# EnvironmentMonitorV5.net
KiCad netlist of a schematic drawn in EAGLE
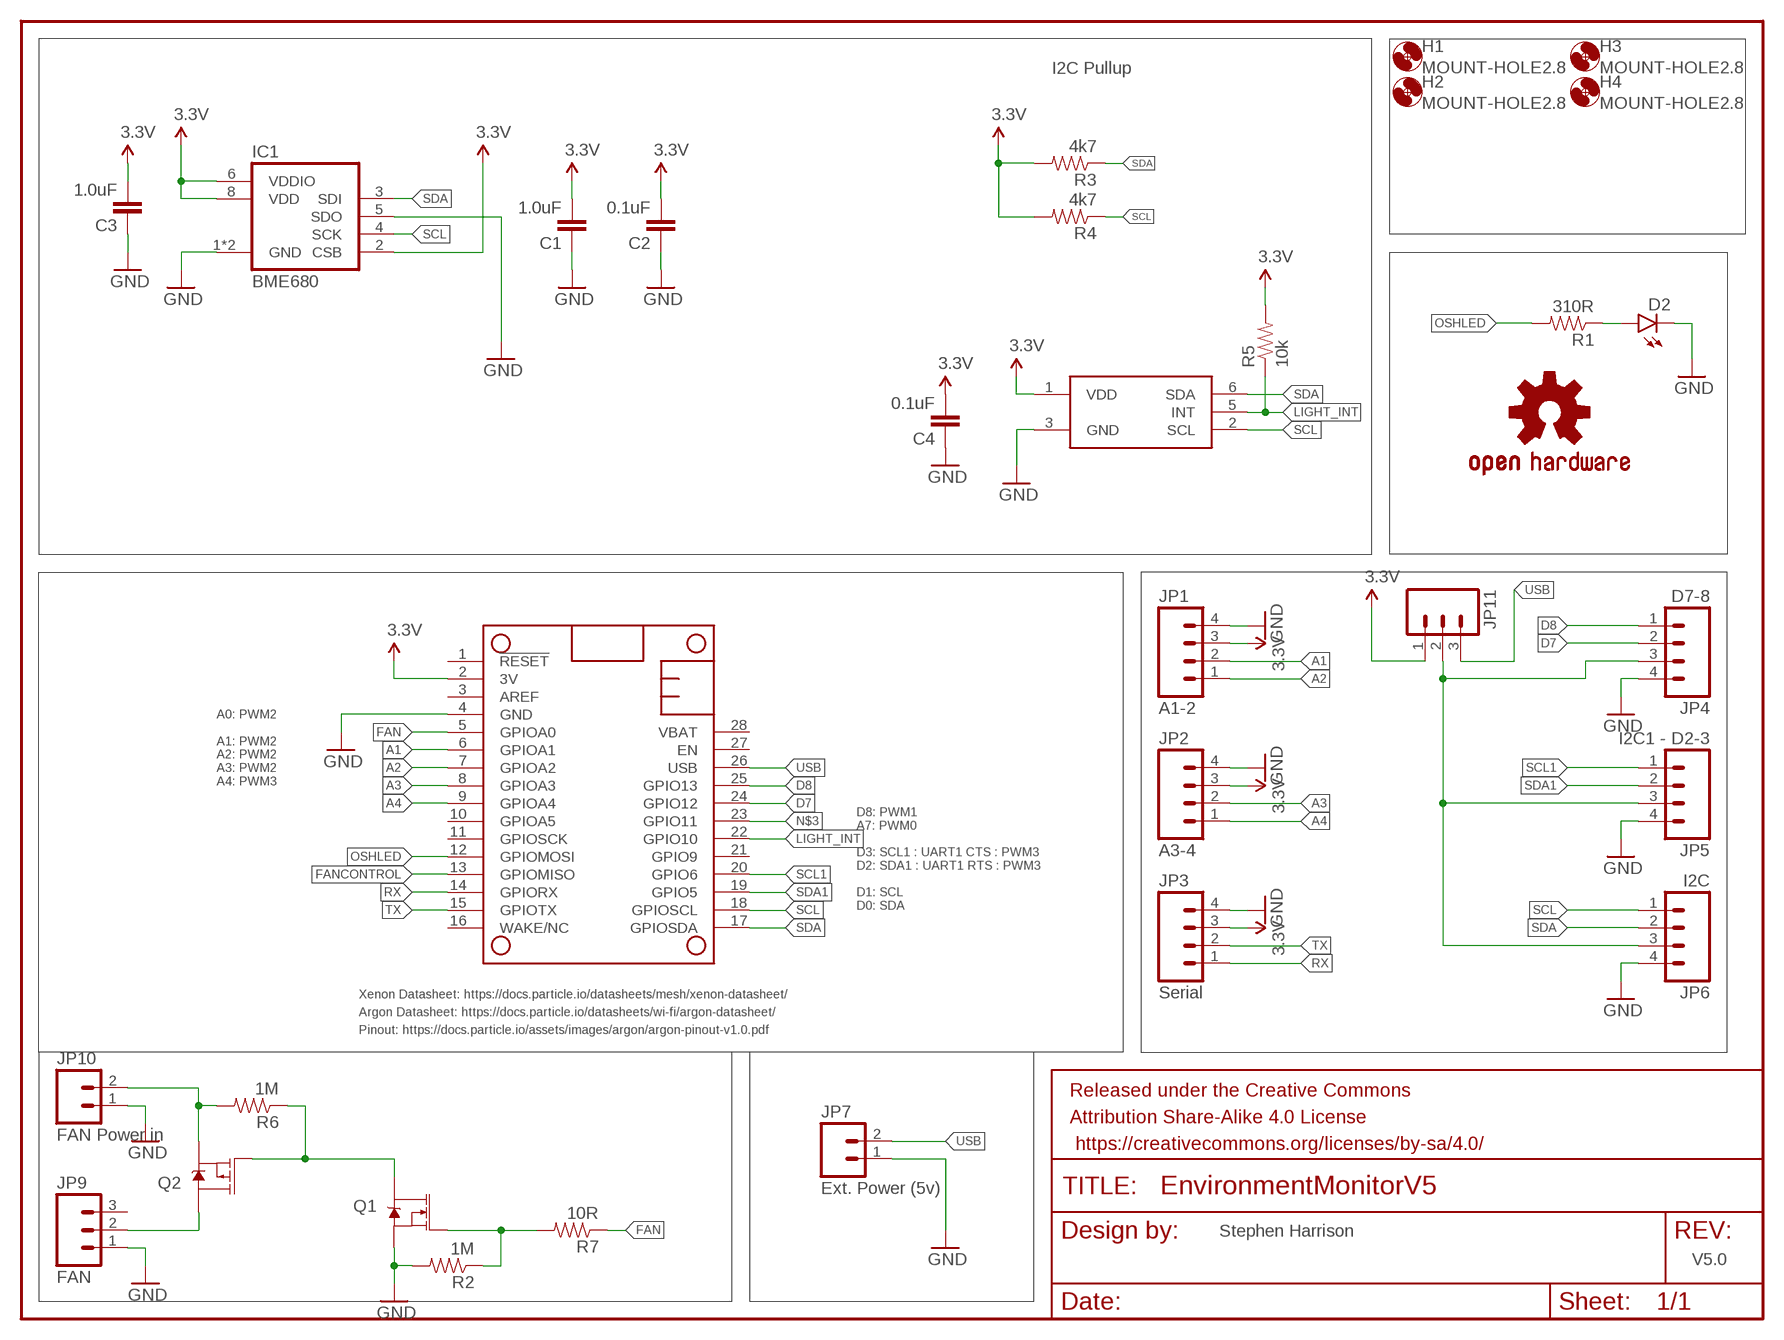
[diagram p0: schematic, sheet 1]

(export (version "E")
  (design (tool "Eeschema 10.0.6"))
  (components
    (comp (ref "C1")
      (value "1.0uF")
      (footprint "eagle-import:0805-CAP")
      (libsource (lib "eagle-import") (part "1.0UF-25V-+80/-20(0805){dblquote}"))
    )
    (comp (ref "C2")
      (value "0.1uF")
      (footprint "eagle-import:0805-CAP")
      (libsource (lib "eagle-import") (part "1.0UF-25V-+80/-20(0805){dblquote}"))
    )
    (comp (ref "C3")
      (value "1.0uF")
      (footprint "eagle-import:0805-CAP")
      (libsource (lib "eagle-import") (part "1.0UF-25V-+80/-20(0805){dblquote}"))
    )
    (comp (ref "C4")
      (value "0.1uF")
      (footprint "eagle-import:0805-CAP")
      (libsource (lib "eagle-import") (part "1.0UF-25V-+80/-20(0805){dblquote}"))
    )
    (comp (ref "D2")
      (value "LED1206-BOTTOM")
      (footprint "eagle-import:LED-1206-BOTTOM")
      (libsource (lib "eagle-import") (part "LED1206-BOTTOM"))
    )
    (comp (ref "FRAME1")
      (value "FRAME-LETTER")
      (footprint "eagle-import:CREATIVE_COMMONS")
      (libsource (lib "eagle-import") (part "FRAME-LETTER"))
    )
    (comp (ref "H1")
      (value "MOUNT-HOLE2.8")
      (footprint "eagle-import:2,8")
      (libsource (lib "eagle-import") (part "MOUNT-HOLE2.8"))
    )
    (comp (ref "H2")
      (value "MOUNT-HOLE2.8")
      (footprint "eagle-import:2,8")
      (libsource (lib "eagle-import") (part "MOUNT-HOLE2.8"))
    )
    (comp (ref "H3")
      (value "MOUNT-HOLE2.8")
      (footprint "eagle-import:2,8")
      (libsource (lib "eagle-import") (part "MOUNT-HOLE2.8"))
    )
    (comp (ref "H4")
      (value "MOUNT-HOLE2.8")
      (footprint "eagle-import:2,8")
      (libsource (lib "eagle-import") (part "MOUNT-HOLE2.8"))
    )
    (comp (ref "IC1")
      (value "BME680")
      (footprint "eagle-import:BME680")
      (libsource (lib "eagle-import") (part "BME680"))
    )
    (comp (ref "IC2")
      (value "TCS3472")
      (footprint "eagle-import:FN-6")
      (libsource (lib "eagle-import") (part "TCS3472"))
    )
    (comp (ref "JP1")
      (value "A1-2")
      (footprint "eagle-import:JST-4-PTH-VERT")
      (libsource (lib "eagle-import") (part "M04JST-PTH-VERT"))
    )
    (comp (ref "JP2")
      (value "A3-4")
      (footprint "eagle-import:JST-4-PTH-VERT")
      (libsource (lib "eagle-import") (part "M04JST-PTH-VERT"))
    )
    (comp (ref "JP3")
      (value "Serial")
      (footprint "eagle-import:JST-4-PTH-VERT")
      (libsource (lib "eagle-import") (part "M04JST-PTH-VERT"))
    )
    (comp (ref "JP4")
      (value "D7-8")
      (footprint "eagle-import:JST-4-PTH-VERT")
      (libsource (lib "eagle-import") (part "M04JST-PTH-VERT"))
    )
    (comp (ref "JP5")
      (value "I2C1 - D2-3")
      (footprint "eagle-import:JST-4-PTH-VERT")
      (libsource (lib "eagle-import") (part "M04JST-PTH-VERT"))
    )
    (comp (ref "JP6")
      (value "I2C")
      (footprint "eagle-import:JST-4-PTH-VERT")
      (libsource (lib "eagle-import") (part "M04JST-PTH-VERT"))
    )
    (comp (ref "JP7")
      (value "Ext. Power (5v)")
      (footprint "eagle-import:MOLEX-1X2_LOCK")
      (libsource (lib "eagle-import") (part "M02POLAR_LOCK"))
    )
    (comp (ref "JP9")
      (value "FAN")
      (footprint "eagle-import:MOLEX-1X3")
      (libsource (lib "eagle-import") (part "M03POLAR"))
    )
    (comp (ref "JP10")
      (value "FAN Power in")
      (footprint "eagle-import:MOLEX-1X2_LOCK")
      (libsource (lib "eagle-import") (part "M02POLAR_LOCK"))
    )
    (comp (ref "JP11")
      (value "M03PTH")
      (footprint "eagle-import:1X03")
      (libsource (lib "eagle-import") (part "M03PTH"))
    )
    (comp (ref "LOGO1")
      (value "OSHW-LOGOM")
      (footprint "eagle-import:OSHW-LOGO-M")
      (libsource (lib "eagle-import") (part "OSHW-LOGOM"))
    )
    (comp (ref "MS1")
      (value "FEATHERWING_NODIM")
      (footprint "eagle-import:FEATHERWING_DIM")
      (libsource (lib "eagle-import") (part "FEATHERWING_NODIM"))
    )
    (comp (ref "Q1")
      (value "220mA/50V/3.5Ω")
      (footprint "eagle-import:SOT23-3")
      (libsource (lib "eagle-import") (part "MOSFET-NCH-BSS138"))
    )
    (comp (ref "Q2")
      (value "4.3A/20V/54mΩ")
      (footprint "eagle-import:SOT23-3")
      (libsource (lib "eagle-import") (part "MOSFET_PCH-IRLML2244"))
    )
    (comp (ref "R1")
      (value "310R")
      (footprint "eagle-import:0805")
      (libsource (lib "eagle-import") (part "RESISTOR0805-RES"))
    )
    (comp (ref "R2")
      (value "1M")
      (footprint "eagle-import:0805")
      (libsource (lib "eagle-import") (part "RESISTOR0805-RES"))
    )
    (comp (ref "R3")
      (value "4k7")
      (footprint "eagle-import:0805")
      (libsource (lib "eagle-import") (part "RESISTOR0805-RES"))
    )
    (comp (ref "R4")
      (value "4k7")
      (footprint "eagle-import:0805")
      (libsource (lib "eagle-import") (part "RESISTOR0805-RES"))
    )
    (comp (ref "R5")
      (value "10k")
      (footprint "eagle-import:0805")
      (libsource (lib "eagle-import") (part "RESISTOR0805-RES"))
    )
    (comp (ref "R6")
      (value "1M")
      (footprint "eagle-import:0805")
      (libsource (lib "eagle-import") (part "RESISTOR0805-RES"))
    )
    (comp (ref "R7")
      (value "10R")
      (footprint "eagle-import:0805")
      (libsource (lib "eagle-import") (part "RESISTOR0805-RES"))
    )
  )
  (nets
    (net (code "1") (name "/VBAT") (class "Default")
      (node (ref "MS1") (pin "28") (pinfunction "VBAT_28") (pintype "power_in"))
    )
    (net (code "2") (name "3.3V") (class "Default")
      (node (ref "C1") (pin "2") (pinfunction "2_2") (pintype "passive"))
      (node (ref "C2") (pin "2") (pinfunction "2_2") (pintype "passive"))
      (node (ref "C3") (pin "2") (pinfunction "2_2") (pintype "passive"))
      (node (ref "C4") (pin "2") (pinfunction "2_2") (pintype "passive"))
      (node (ref "IC1") (pin "2") (pinfunction "CSB_2") (pintype "input"))
      (node (ref "IC1") (pin "6") (pinfunction "VDDIO_6") (pintype "power_in"))
      (node (ref "IC1") (pin "8") (pinfunction "VDD_8") (pintype "power_in"))
      (node (ref "IC2") (pin "1") (pinfunction "VDD_1") (pintype "bidirectional"))
      (node (ref "JP1") (pin "3") (pinfunction "3_3") (pintype "passive"))
      (node (ref "JP11") (pin "1") (pinfunction "1_1") (pintype "passive"))
      (node (ref "JP2") (pin "3") (pinfunction "3_3") (pintype "passive"))
      (node (ref "JP3") (pin "3") (pinfunction "3_3") (pintype "passive"))
      (node (ref "MS1") (pin "2") (pinfunction "3V_2") (pintype "power_in"))
      (node (ref "R3") (pin "2") (pinfunction "2_2") (pintype "passive"))
      (node (ref "R4") (pin "2") (pinfunction "2_2") (pintype "passive"))
      (node (ref "R5") (pin "2") (pinfunction "2_2") (pintype "passive"))
    )
    (net (code "3") (name "A1") (class "Default")
      (node (ref "JP1") (pin "2") (pinfunction "2_2") (pintype "passive"))
      (node (ref "MS1") (pin "6") (pinfunction "GPIOA1_6") (pintype "bidirectional"))
    )
    (net (code "4") (name "A2") (class "Default")
      (node (ref "JP1") (pin "1") (pinfunction "1_1") (pintype "passive"))
      (node (ref "MS1") (pin "7") (pinfunction "GPIOA2_7") (pintype "bidirectional"))
    )
    (net (code "5") (name "A3") (class "Default")
      (node (ref "JP2") (pin "2") (pinfunction "2_2") (pintype "passive"))
      (node (ref "MS1") (pin "8") (pinfunction "GPIOA3_8") (pintype "bidirectional"))
    )
    (net (code "6") (name "A4") (class "Default")
      (node (ref "JP2") (pin "1") (pinfunction "1_1") (pintype "passive"))
      (node (ref "MS1") (pin "9") (pinfunction "GPIOA4_9") (pintype "bidirectional"))
    )
    (net (code "7") (name "D7") (class "Default")
      (node (ref "JP4") (pin "2") (pinfunction "2_2") (pintype "passive"))
      (node (ref "MS1") (pin "24") (pinfunction "GPIO12_24") (pintype "bidirectional"))
    )
    (net (code "8") (name "D8") (class "Default")
      (node (ref "JP4") (pin "1") (pinfunction "1_1") (pintype "passive"))
      (node (ref "MS1") (pin "25") (pinfunction "GPIO13_25") (pintype "bidirectional"))
    )
    (net (code "9") (name "FAN") (class "Default")
      (node (ref "MS1") (pin "5") (pinfunction "GPIOA0_5") (pintype "bidirectional"))
      (node (ref "R7") (pin "1") (pinfunction "1_1") (pintype "passive"))
    )
    (net (code "10") (name "FANCONTROL") (class "Default")
      (node (ref "MS1") (pin "13") (pinfunction "GPIOMISO_13") (pintype "bidirectional"))
    )
    (net (code "11") (name "GND") (class "Default")
      (node (ref "C1") (pin "1") (pinfunction "1_1") (pintype "passive"))
      (node (ref "C2") (pin "1") (pinfunction "1_1") (pintype "passive"))
      (node (ref "C3") (pin "1") (pinfunction "1_1") (pintype "passive"))
      (node (ref "C4") (pin "1") (pinfunction "1_1") (pintype "passive"))
      (node (ref "D2") (pin "C") (pinfunction "C_C") (pintype "passive"))
      (node (ref "IC1") (pin "1") (pinfunction "GND_1") (pintype "power_in"))
      (node (ref "IC1") (pin "5") (pinfunction "SDO_5") (pintype "output"))
      (node (ref "IC1") (pin "7") (pinfunction "GND_7") (pintype "power_in"))
      (node (ref "IC2") (pin "3") (pinfunction "GND_3") (pintype "bidirectional"))
      (node (ref "JP1") (pin "4") (pinfunction "4_4") (pintype "passive"))
      (node (ref "JP10") (pin "1") (pinfunction "1_1") (pintype "passive"))
      (node (ref "JP2") (pin "4") (pinfunction "4_4") (pintype "passive"))
      (node (ref "JP3") (pin "4") (pinfunction "4_4") (pintype "passive"))
      (node (ref "JP4") (pin "4") (pinfunction "4_4") (pintype "passive"))
      (node (ref "JP5") (pin "4") (pinfunction "4_4") (pintype "passive"))
      (node (ref "JP6") (pin "4") (pinfunction "4_4") (pintype "passive"))
      (node (ref "JP7") (pin "1") (pinfunction "1_1") (pintype "passive"))
      (node (ref "JP9") (pin "1") (pinfunction "1_1") (pintype "passive"))
      (node (ref "MS1") (pin "4") (pinfunction "GND_4") (pintype "power_in"))
      (node (ref "Q1") (pin "2") (pinfunction "S_2") (pintype "bidirectional"))
      (node (ref "R2") (pin "2") (pinfunction "2_2") (pintype "passive"))
    )
    (net (code "12") (name "LIGHT_INT") (class "Default")
      (node (ref "IC2") (pin "5") (pinfunction "INT_5") (pintype "bidirectional"))
      (node (ref "MS1") (pin "22") (pinfunction "GPIO10_22") (pintype "bidirectional"))
      (node (ref "R5") (pin "1") (pinfunction "1_1") (pintype "passive"))
    )
    (net (code "13") (name "N$3") (class "Default")
      (node (ref "MS1") (pin "23") (pinfunction "GPIO11_23") (pintype "bidirectional"))
    )
    (net (code "14") (name "Net-(D2-PadA)") (class "Default")
      (node (ref "D2") (pin "A") (pinfunction "A_A") (pintype "passive"))
      (node (ref "R1") (pin "1") (pinfunction "1_1") (pintype "passive"))
    )
    (net (code "15") (name "Net-(JP11-Pad2)") (class "Default")
      (node (ref "JP11") (pin "2") (pinfunction "2_2") (pintype "passive"))
      (node (ref "JP4") (pin "3") (pinfunction "3_3") (pintype "passive"))
      (node (ref "JP5") (pin "3") (pinfunction "3_3") (pintype "passive"))
      (node (ref "JP6") (pin "3") (pinfunction "3_3") (pintype "passive"))
    )
    (net (code "16") (name "Net-(Q1-D)") (class "Default")
      (node (ref "Q1") (pin "3") (pinfunction "D_3") (pintype "bidirectional"))
      (node (ref "Q2") (pin "1") (pinfunction "G_1") (pintype "bidirectional"))
      (node (ref "R6") (pin "1") (pinfunction "1_1") (pintype "passive"))
    )
    (net (code "17") (name "Net-(Q1-G)") (class "Default")
      (node (ref "Q1") (pin "1") (pinfunction "G_1") (pintype "bidirectional"))
      (node (ref "R2") (pin "1") (pinfunction "1_1") (pintype "passive"))
      (node (ref "R7") (pin "2") (pinfunction "2_2") (pintype "passive"))
    )
    (net (code "18") (name "Net-(Q2-D)") (class "Default")
      (node (ref "JP9") (pin "2") (pinfunction "2_2") (pintype "passive"))
      (node (ref "Q2") (pin "3") (pinfunction "D_3") (pintype "bidirectional"))
    )
    (net (code "19") (name "Net-(Q2-S)") (class "Default")
      (node (ref "JP10") (pin "2") (pinfunction "2_2") (pintype "passive"))
      (node (ref "Q2") (pin "2") (pinfunction "S_2") (pintype "bidirectional"))
      (node (ref "R6") (pin "2") (pinfunction "2_2") (pintype "passive"))
    )
    (net (code "20") (name "OSHLED") (class "Default")
      (node (ref "MS1") (pin "12") (pinfunction "GPIOMOSI_12") (pintype "bidirectional"))
      (node (ref "R1") (pin "2") (pinfunction "2_2") (pintype "passive"))
    )
    (net (code "21") (name "RX") (class "Default")
      (node (ref "JP3") (pin "1") (pinfunction "1_1") (pintype "passive"))
      (node (ref "MS1") (pin "14") (pinfunction "GPIORX_14") (pintype "bidirectional"))
    )
    (net (code "22") (name "SCL") (class "Default")
      (node (ref "IC1") (pin "4") (pinfunction "SCK_4") (pintype "input"))
      (node (ref "IC2") (pin "2") (pinfunction "SCL_2") (pintype "bidirectional"))
      (node (ref "JP6") (pin "1") (pinfunction "1_1") (pintype "passive"))
      (node (ref "MS1") (pin "18") (pinfunction "GPIOSCL_18") (pintype "bidirectional"))
      (node (ref "R4") (pin "1") (pinfunction "1_1") (pintype "passive"))
    )
    (net (code "23") (name "SCL1") (class "Default")
      (node (ref "JP5") (pin "1") (pinfunction "1_1") (pintype "passive"))
      (node (ref "MS1") (pin "20") (pinfunction "GPIO6_20") (pintype "bidirectional"))
    )
    (net (code "24") (name "SDA") (class "Default")
      (node (ref "IC1") (pin "3") (pinfunction "SDI_3") (pintype "input"))
      (node (ref "IC2") (pin "6") (pinfunction "SDA_6") (pintype "bidirectional"))
      (node (ref "JP6") (pin "2") (pinfunction "2_2") (pintype "passive"))
      (node (ref "MS1") (pin "17") (pinfunction "GPIOSDA_17") (pintype "bidirectional"))
      (node (ref "R3") (pin "1") (pinfunction "1_1") (pintype "passive"))
    )
    (net (code "25") (name "SDA1") (class "Default")
      (node (ref "JP5") (pin "2") (pinfunction "2_2") (pintype "passive"))
      (node (ref "MS1") (pin "19") (pinfunction "GPIO5_19") (pintype "bidirectional"))
    )
    (net (code "26") (name "TX") (class "Default")
      (node (ref "JP3") (pin "2") (pinfunction "2_2") (pintype "passive"))
      (node (ref "MS1") (pin "15") (pinfunction "GPIOTX_15") (pintype "bidirectional"))
    )
    (net (code "27") (name "USB") (class "Default")
      (node (ref "JP11") (pin "3") (pinfunction "3_3") (pintype "passive"))
      (node (ref "JP7") (pin "2") (pinfunction "2_2") (pintype "passive"))
      (node (ref "MS1") (pin "26") (pinfunction "USB_26") (pintype "power_in"))
    )
    (net (code "28") (name "unconnected-(JP9-Pad3)") (class "Default")
      (node (ref "JP9") (pin "3") (pinfunction "3_3") (pintype "passive"))
    )
    (net (code "29") (name "unconnected-(MS1-AREF-Pad3)") (class "Default")
      (node (ref "MS1") (pin "3") (pinfunction "AREF_3") (pintype "passive"))
    )
    (net (code "30") (name "unconnected-(MS1-EN-Pad27)") (class "Default")
      (node (ref "MS1") (pin "27") (pinfunction "EN_27") (pintype "passive"))
    )
    (net (code "31") (name "unconnected-(MS1-GPIO9-Pad21)") (class "Default")
      (node (ref "MS1") (pin "21") (pinfunction "GPIO9_21") (pintype "bidirectional"))
    )
    (net (code "32") (name "unconnected-(MS1-GPIOA5-Pad10)") (class "Default")
      (node (ref "MS1") (pin "10") (pinfunction "GPIOA5_10") (pintype "bidirectional"))
    )
    (net (code "33") (name "unconnected-(MS1-GPIOSCK-Pad11)") (class "Default")
      (node (ref "MS1") (pin "11") (pinfunction "GPIOSCK_11") (pintype "bidirectional"))
    )
    (net (code "34") (name "unconnected-(MS1-WAKE{slash}NC-Pad16)") (class "Default")
      (node (ref "MS1") (pin "16") (pinfunction "WAKE/NC_16") (pintype "passive"))
    )
    (net (code "35") (name "unconnected-(MS1-~{RESET}-Pad1)") (class "Default")
      (node (ref "MS1") (pin "1") (pinfunction "~{RESET}_1") (pintype "input"))
    )
  )
)
